# v21.net
KiCad netlist of a schematic drawn in EAGLE
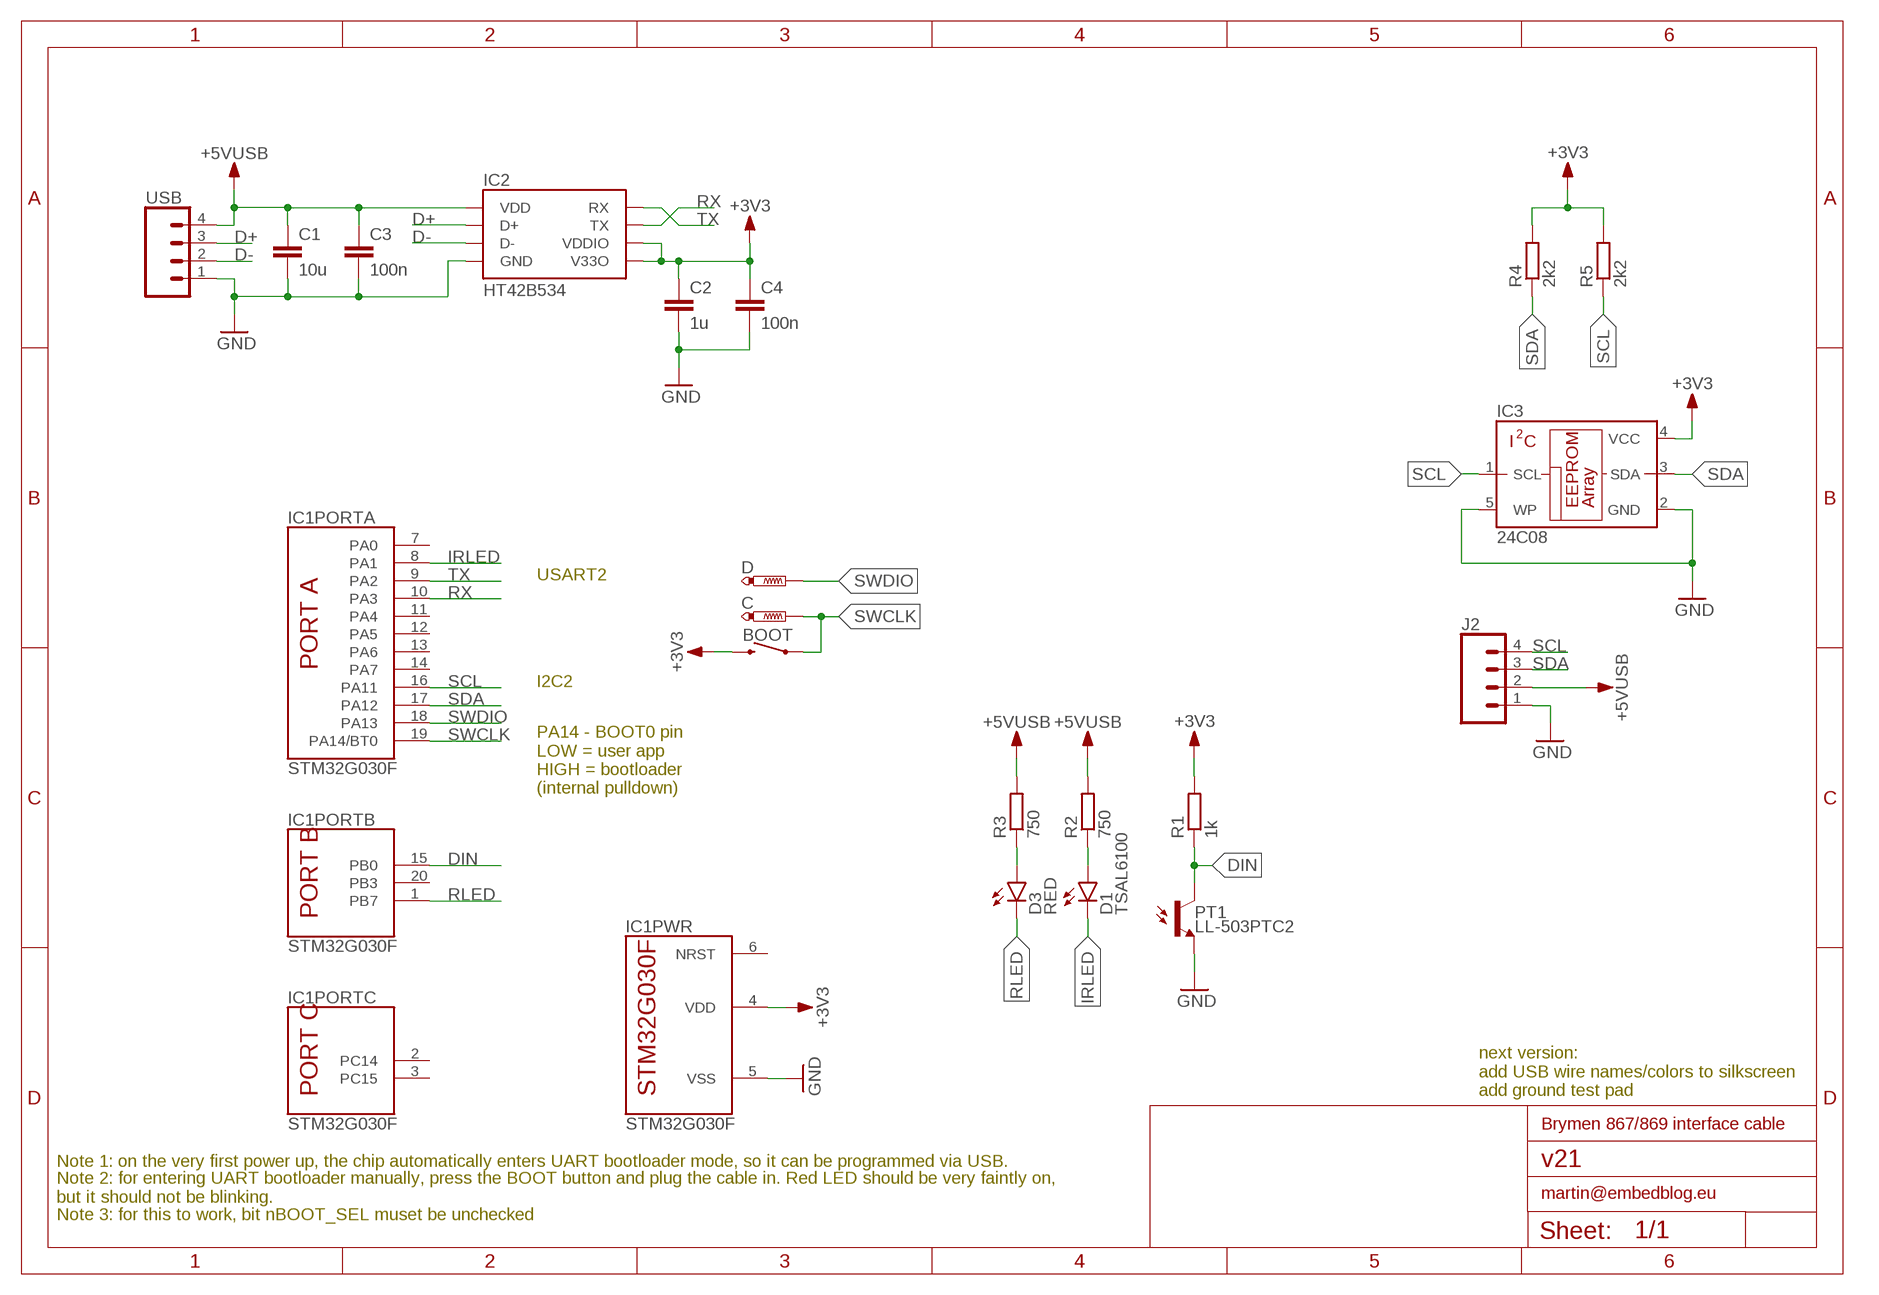
[diagram p0: schematic, sheet 1]

(export (version "E")
  (design (tool "Eeschema 10.0.6"))
  (components
    (comp (ref "BOOT")
      (value "MOMENTARY-SWITCH-SPST-SMD-5.2MM")
      (footprint "eagle-import:TACTILE_SWITCH_SMD_5.2MM")
      (libsource (lib "eagle-import") (part "MOMENTARY-SWITCH-SPST-SMD-5.2MM"))
    )
    (comp (ref "C")
      (value "PTR1B1,27")
      (footprint "eagle-import:B1,27")
      (libsource (lib "eagle-import") (part "PTR1B1,27"))
    )
    (comp (ref "C1")
      (value "10u")
      (footprint "eagle-import:C0603")
      (libsource (lib "eagle-import") (part "C0603"))
    )
    (comp (ref "C2")
      (value "1u")
      (footprint "eagle-import:C0603")
      (libsource (lib "eagle-import") (part "C0603"))
    )
    (comp (ref "C3")
      (value "100n")
      (footprint "eagle-import:C0603")
      (libsource (lib "eagle-import") (part "C0603"))
    )
    (comp (ref "C4")
      (value "100n")
      (footprint "eagle-import:C0603")
      (libsource (lib "eagle-import") (part "C0603"))
    )
    (comp (ref "D")
      (value "PTR1B1,27")
      (footprint "eagle-import:B1,27")
      (libsource (lib "eagle-import") (part "PTR1B1,27"))
    )
    (comp (ref "D1")
      (value "TSAL6100")
      (footprint "eagle-import:LED_5MM")
      (libsource (lib "eagle-import") (part "LED5MM"))
    )
    (comp (ref "D3")
      (value "RED")
      (footprint "eagle-import:LED-0603")
      (libsource (lib "eagle-import") (part "LED0603"))
    )
    (comp (ref "IC1")
      (value "STM32G030F")
      (footprint "eagle-import:TSSOP20")
      (libsource (lib "eagle-import") (part "STM32G030F"))
    )
    (comp (ref "IC2")
      (value "HT42B534")
      (footprint "eagle-import:SOP8")
      (libsource (lib "eagle-import") (part "HT42B534"))
    )
    (comp (ref "IC3")
      (value "24C08")
      (footprint "eagle-import:SOT23-5")
      (libsource (lib "eagle-import") (part "EEPROM_24"))
    )
    (comp (ref "J2")
      (value "CONN_041.27MM")
      (footprint "eagle-import:1X04_1.27MM")
      (libsource (lib "eagle-import") (part "CONN_041.27MM"))
    )
    (comp (ref "PT1")
      (value "LL-503PTC2")
      (footprint "eagle-import:LED5MM")
      (libsource (lib "eagle-import") (part "LL-503_PHOTOTRANSISTOR"))
    )
    (comp (ref "R1")
      (value "1k")
      (footprint "eagle-import:R0603")
      (libsource (lib "eagle-import") (part "R0603"))
    )
    (comp (ref "R2")
      (value "750")
      (footprint "eagle-import:R0603")
      (libsource (lib "eagle-import") (part "R0603"))
    )
    (comp (ref "R3")
      (value "750")
      (footprint "eagle-import:R0603")
      (libsource (lib "eagle-import") (part "R0603"))
    )
    (comp (ref "R4")
      (value "2k2")
      (footprint "eagle-import:R0603")
      (libsource (lib "eagle-import") (part "R0603"))
    )
    (comp (ref "R5")
      (value "2k2")
      (footprint "eagle-import:R0603")
      (libsource (lib "eagle-import") (part "R0603"))
    )
    (comp (ref "USB")
      (value "CONN_04")
      (footprint "eagle-import:1X04")
      (libsource (lib "eagle-import") (part "CONN_04"))
    )
  )
  (nets
    (net (code "1") (name "+3V3") (class "Default")
      (node (ref "BOOT") (pin "3") (pinfunction "2_3") (pintype "passive"))
      (node (ref "C2") (pin "1") (pinfunction "1_1") (pintype "passive"))
      (node (ref "C4") (pin "1") (pinfunction "1_1") (pintype "passive"))
      (node (ref "IC1") (pin "4") (pinfunction "VDD_4") (pintype "power_in"))
      (node (ref "IC2") (pin "3") (pinfunction "VDDIO_3") (pintype "input"))
      (node (ref "IC2") (pin "8") (pinfunction "V33O_8") (pintype "output"))
      (node (ref "IC3") (pin "4") (pinfunction "VCC_4") (pintype "power_in"))
      (node (ref "R1") (pin "2") (pinfunction "2_2") (pintype "passive"))
      (node (ref "R4") (pin "2") (pinfunction "2_2") (pintype "passive"))
      (node (ref "R5") (pin "2") (pinfunction "2_2") (pintype "passive"))
    )
    (net (code "2") (name "+5VUSB") (class "Default")
      (node (ref "C1") (pin "1") (pinfunction "1_1") (pintype "passive"))
      (node (ref "C3") (pin "1") (pinfunction "1_1") (pintype "passive"))
      (node (ref "IC2") (pin "7") (pinfunction "VDD_7") (pintype "power_in"))
      (node (ref "J2") (pin "2") (pinfunction "2_2") (pintype "passive"))
      (node (ref "R2") (pin "2") (pinfunction "2_2") (pintype "passive"))
      (node (ref "R3") (pin "2") (pinfunction "2_2") (pintype "passive"))
      (node (ref "USB") (pin "4") (pinfunction "4_4") (pintype "passive"))
    )
    (net (code "3") (name "/D+") (class "Default")
      (node (ref "IC2") (pin "5") (pinfunction "D+_5") (pintype "bidirectional"))
      (node (ref "USB") (pin "3") (pinfunction "3_3") (pintype "passive"))
    )
    (net (code "4") (name "/D-") (class "Default")
      (node (ref "IC2") (pin "6") (pinfunction "D-_6") (pintype "bidirectional"))
      (node (ref "USB") (pin "2") (pinfunction "2_2") (pintype "passive"))
    )
    (net (code "5") (name "/RX") (class "Default")
      (node (ref "IC1") (pin "10") (pinfunction "PA3_10") (pintype "bidirectional"))
      (node (ref "IC2") (pin "2") (pinfunction "TX_2") (pintype "output"))
    )
    (net (code "6") (name "/TX") (class "Default")
      (node (ref "IC1") (pin "9") (pinfunction "PA2_9") (pintype "bidirectional"))
      (node (ref "IC2") (pin "4") (pinfunction "RX_4") (pintype "input"))
    )
    (net (code "7") (name "DIN") (class "Default")
      (node (ref "IC1") (pin "15") (pinfunction "PB0_15") (pintype "bidirectional"))
      (node (ref "PT1") (pin "K") (pinfunction "C_K") (pintype "passive"))
      (node (ref "R1") (pin "1") (pinfunction "1_1") (pintype "passive"))
    )
    (net (code "8") (name "GND") (class "Default")
      (node (ref "C1") (pin "2") (pinfunction "2_2") (pintype "passive"))
      (node (ref "C2") (pin "2") (pinfunction "2_2") (pintype "passive"))
      (node (ref "C3") (pin "2") (pinfunction "2_2") (pintype "passive"))
      (node (ref "C4") (pin "2") (pinfunction "2_2") (pintype "passive"))
      (node (ref "IC1") (pin "5") (pinfunction "VSS_5") (pintype "power_in"))
      (node (ref "IC2") (pin "1") (pinfunction "GND_1") (pintype "power_in"))
      (node (ref "IC3") (pin "2") (pinfunction "GND_2") (pintype "power_in"))
      (node (ref "IC3") (pin "5") (pinfunction "WP_5") (pintype "input"))
      (node (ref "J2") (pin "1") (pinfunction "1_1") (pintype "passive"))
      (node (ref "PT1") (pin "A") (pinfunction "E_A") (pintype "passive"))
      (node (ref "USB") (pin "1") (pinfunction "1_1") (pintype "passive"))
    )
    (net (code "9") (name "IRLED") (class "Default")
      (node (ref "D1") (pin "K") (pinfunction "C_K") (pintype "passive"))
      (node (ref "IC1") (pin "8") (pinfunction "PA1_8") (pintype "bidirectional"))
    )
    (net (code "10") (name "Net-(D1-PadA)") (class "Default")
      (node (ref "D1") (pin "A") (pinfunction "A_A") (pintype "passive"))
      (node (ref "R2") (pin "1") (pinfunction "1_1") (pintype "passive"))
    )
    (net (code "11") (name "Net-(D3-PadA)") (class "Default")
      (node (ref "D3") (pin "A") (pinfunction "A_A") (pintype "passive"))
      (node (ref "R3") (pin "1") (pinfunction "1_1") (pintype "passive"))
    )
    (net (code "12") (name "RLED") (class "Default")
      (node (ref "D3") (pin "C") (pinfunction "C_C") (pintype "passive"))
      (node (ref "IC1") (pin "1") (pinfunction "PB7_1") (pintype "bidirectional"))
    )
    (net (code "13") (name "SCL") (class "Default")
      (node (ref "IC1") (pin "16") (pinfunction "PA11_16") (pintype "bidirectional"))
      (node (ref "IC3") (pin "1") (pinfunction "SCL_1") (pintype "input"))
      (node (ref "J2") (pin "4") (pinfunction "4_4") (pintype "passive"))
      (node (ref "R5") (pin "1") (pinfunction "1_1") (pintype "passive"))
    )
    (net (code "14") (name "SDA") (class "Default")
      (node (ref "IC1") (pin "17") (pinfunction "PA12_17") (pintype "bidirectional"))
      (node (ref "IC3") (pin "3") (pinfunction "SDA_3") (pintype "bidirectional"))
      (node (ref "J2") (pin "3") (pinfunction "3_3") (pintype "passive"))
      (node (ref "R4") (pin "1") (pinfunction "1_1") (pintype "passive"))
    )
    (net (code "15") (name "SWCLK") (class "Default")
      (node (ref "BOOT") (pin "1") (pinfunction "1_1") (pintype "passive"))
      (node (ref "C") (pin "TP") (pinfunction "TP_TP") (pintype "input"))
      (node (ref "IC1") (pin "19") (pinfunction "PA14/BT0_19") (pintype "bidirectional"))
    )
    (net (code "16") (name "SWDIO") (class "Default")
      (node (ref "D") (pin "TP") (pinfunction "TP_TP") (pintype "input"))
      (node (ref "IC1") (pin "18") (pinfunction "PA13_18") (pintype "bidirectional"))
    )
    (net (code "17") (name "unconnected-(IC1A-PA0-Pad7)") (class "Default")
      (node (ref "IC1") (pin "7") (pinfunction "PA0_7") (pintype "bidirectional"))
    )
    (net (code "18") (name "unconnected-(IC1A-PA4-Pad11)") (class "Default")
      (node (ref "IC1") (pin "11") (pinfunction "PA4_11") (pintype "bidirectional"))
    )
    (net (code "19") (name "unconnected-(IC1A-PA5-Pad12)") (class "Default")
      (node (ref "IC1") (pin "12") (pinfunction "PA5_12") (pintype "bidirectional"))
    )
    (net (code "20") (name "unconnected-(IC1A-PA6-Pad13)") (class "Default")
      (node (ref "IC1") (pin "13") (pinfunction "PA6_13") (pintype "bidirectional"))
    )
    (net (code "21") (name "unconnected-(IC1A-PA7-Pad14)") (class "Default")
      (node (ref "IC1") (pin "14") (pinfunction "PA7_14") (pintype "bidirectional"))
    )
    (net (code "22") (name "unconnected-(IC1B-PB3-Pad20)") (class "Default")
      (node (ref "IC1") (pin "20") (pinfunction "PB3_20") (pintype "bidirectional"))
    )
    (net (code "23") (name "unconnected-(IC1C-PC14-Pad2)") (class "Default")
      (node (ref "IC1") (pin "2") (pinfunction "PC14_2") (pintype "bidirectional"))
    )
    (net (code "24") (name "unconnected-(IC1C-PC15-Pad3)") (class "Default")
      (node (ref "IC1") (pin "3") (pinfunction "PC15_3") (pintype "bidirectional"))
    )
    (net (code "25") (name "unconnected-(IC1D-NRST-Pad6)") (class "Default")
      (node (ref "IC1") (pin "6") (pinfunction "NRST_6") (pintype "bidirectional"))
    )
  )
)
